# sche_v1.net
KiCad netlist of a schematic drawn in Altium Designer
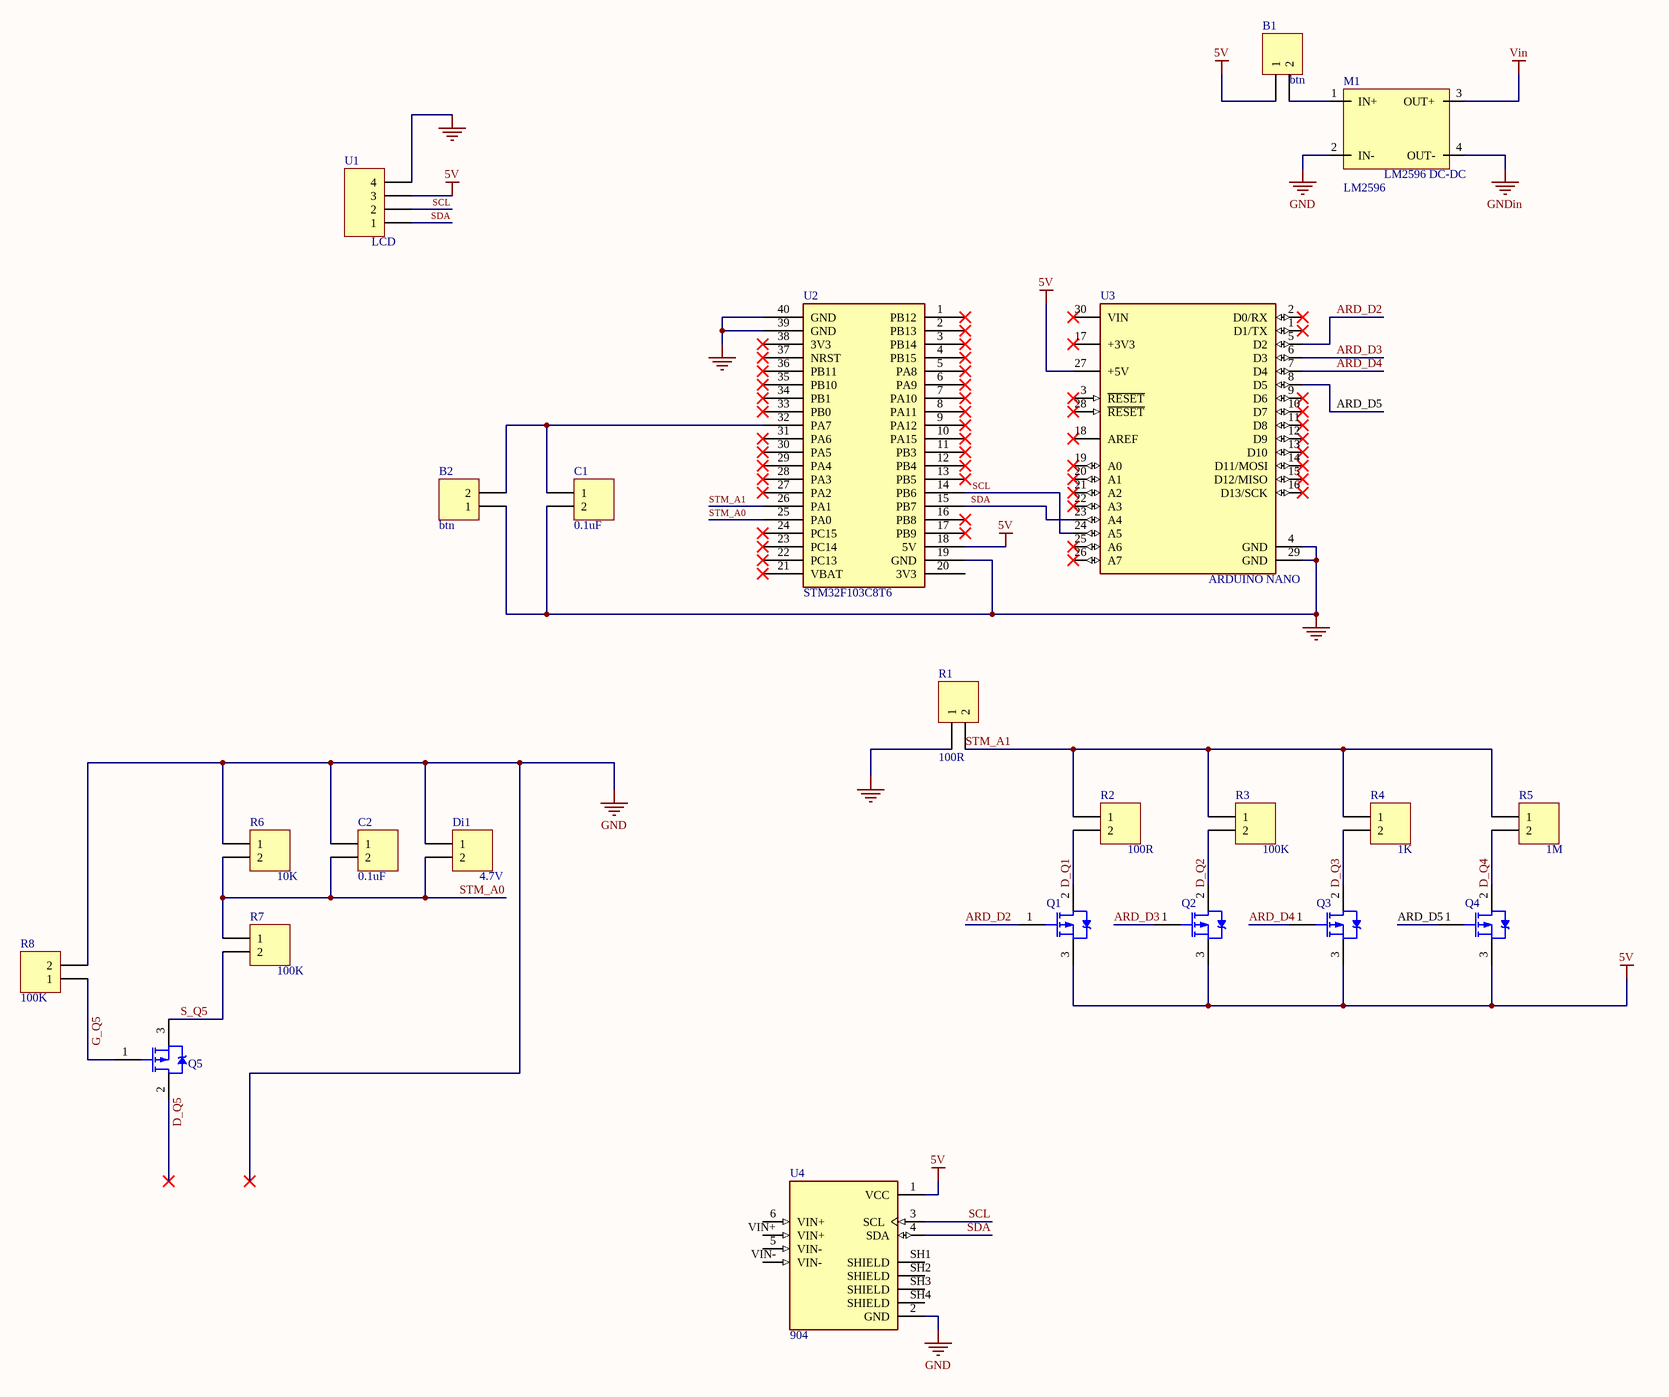
[diagram p0: sche_v1.SchDoc]

(export (version "E")
  (design (tool "Eeschema 10.0.6"))
  (components
    (comp (ref "B1")
      (value "btn")
      (footprint "JP2")
      (description "Header, 2-Pin")
      (fields (field (name "PUBLISHER") "Altium Limited"))
      (libsource (lib "") (part "Header 2_1"))
    )
    (comp (ref "B2")
      (value "btn")
      (footprint "JP2")
      (description "Header, 2-Pin")
      (fields (field (name "PUBLISHER") "Altium Limited"))
      (libsource (lib "") (part "Header 2_2"))
    )
    (comp (ref "C1")
      (value "0.1uF")
      (footprint "JP2")
      (description "Header, 2-Pin")
      (fields (field (name "PUBLISHER") "Altium Limited"))
      (libsource (lib "PIF_Library") (part "Header 2"))
    )
    (comp (ref "C2")
      (value "0.1uF")
      (footprint "JP2")
      (description "Header, 2-Pin")
      (fields (field (name "PUBLISHER") "Altium Limited"))
      (libsource (lib "PIF_Library") (part "Header 2"))
    )
    (comp (ref "Di1")
      (value "4.7V")
      (footprint "JP2")
      (description "Header, 2-Pin")
      (fields (field (name "PUBLISHER") "Altium Limited"))
      (libsource (lib "PIF_Library") (part "Header 2"))
    )
    (comp (ref "M1")
      (value "LM2596")
      (footprint "LM2596")
      (description "Module")
      (libsource (lib "LM2596") (part "LM2596"))
    )
    (comp (ref "Q1")
      (value "IRF9540N")
      (footprint "IRF9540N-TO-220AB")
      (description "MOSFET P-CH, 100V, 23A, 117mOhm, TO220AB")
      (libsource (lib "Altium_MOSFET") (part "IRF9540N"))
    )
    (comp (ref "Q2")
      (value "IRF9540N")
      (footprint "IRF9540N-TO-220AB")
      (description "MOSFET P-CH, 100V, 23A, 117mOhm, TO220AB")
      (libsource (lib "Altium_MOSFET") (part "IRF9540N"))
    )
    (comp (ref "Q3")
      (value "IRF9540N")
      (footprint "IRF9540N-TO-220AB")
      (description "MOSFET P-CH, 100V, 23A, 117mOhm, TO220AB")
      (libsource (lib "Altium_MOSFET") (part "IRF9540N"))
    )
    (comp (ref "Q4")
      (value "IRF9540N")
      (footprint "IRF9540N-TO-220AB")
      (description "MOSFET P-CH, 100V, 23A, 117mOhm, TO220AB")
      (libsource (lib "Altium_MOSFET") (part "IRF9540N"))
    )
    (comp (ref "Q5")
      (value "IRF9540N")
      (footprint "IRF9540N-TO-220AB")
      (description "MOSFET P-CH, 100V, 23A, 117mOhm, TO220AB")
      (libsource (lib "Altium_MOSFET") (part "IRF9540N"))
    )
    (comp (ref "R1")
      (value "100R")
      (footprint "JP2")
      (description "Header, 2-Pin")
      (fields (field (name "PUBLISHER") "Altium Limited"))
      (libsource (lib "") (part "Header 2_1"))
    )
    (comp (ref "R2")
      (value "100R")
      (footprint "JP2")
      (description "Header, 2-Pin")
      (fields (field (name "PUBLISHER") "Altium Limited"))
      (libsource (lib "PIF_Library") (part "Header 2"))
    )
    (comp (ref "R3")
      (value "100K")
      (footprint "JP2")
      (description "Header, 2-Pin")
      (fields (field (name "PUBLISHER") "Altium Limited"))
      (libsource (lib "PIF_Library") (part "Header 2"))
    )
    (comp (ref "R4")
      (value "1K")
      (footprint "JP2")
      (description "Header, 2-Pin")
      (fields (field (name "PUBLISHER") "Altium Limited"))
      (libsource (lib "PIF_Library") (part "Header 2"))
    )
    (comp (ref "R5")
      (value "1M")
      (footprint "JP2")
      (description "Header, 2-Pin")
      (fields (field (name "PUBLISHER") "Altium Limited"))
      (libsource (lib "PIF_Library") (part "Header 2"))
    )
    (comp (ref "R6")
      (value "10K")
      (footprint "JP2")
      (description "Header, 2-Pin")
      (fields (field (name "PUBLISHER") "Altium Limited"))
      (libsource (lib "PIF_Library") (part "Header 2"))
    )
    (comp (ref "R7")
      (value "100K")
      (footprint "JP2")
      (description "Header, 2-Pin")
      (fields (field (name "PUBLISHER") "Altium Limited"))
      (libsource (lib "PIF_Library") (part "Header 2"))
    )
    (comp (ref "R8")
      (value "100K")
      (footprint "JP2")
      (description "Header, 2-Pin")
      (fields (field (name "PUBLISHER") "Altium Limited"))
      (libsource (lib "") (part "Header 2_2"))
    )
    (comp (ref "U1")
      (value "LCD")
      (footprint "JP4")
      (description "Header, 4-Pin")
      (fields (field (name "PUBLISHER") "Altium Limited"))
      (libsource (lib "PIF_Library") (part "Header 4"))
    )
    (comp (ref "U2")
      (value "STM32F103C8T6")
      (footprint "Stm32 BluePill")
      (description "Designed By @Alixahedi")
      (libsource (lib "Stm32 Blue Pill") (part "BluePill"))
    )
    (comp (ref "U3")
      (value "ARDUINO NANO")
      (footprint "FP-A000005-MFG")
      (description "ARDUINO NANO ATMEGA328 EVAL BRD")
      (libsource (lib "Altium Content Vault") (part "d190c066e99afd1c6882cf92e11b2cc"))
    )
    (comp (ref "U4")
      (value "904")
      (footprint "MODULE_904")
      (fields (field (name "MF") "Adafruit Industries"))
      (libsource (lib "904") (part "904"))
    )
  )
  (nets
    (net (code "1") (name "/ARD_D2") (class "Default")
      (node (ref "Q1") (pin "1") (pinfunction "G_1") (pintype "passive"))
      (node (ref "U3") (pin "5") (pinfunction "D2_5") (pintype "bidirectional"))
    )
    (net (code "2") (name "/ARD_D3") (class "Default")
      (node (ref "Q2") (pin "1") (pinfunction "G_1") (pintype "passive"))
      (node (ref "U3") (pin "6") (pinfunction "D3_6") (pintype "bidirectional"))
    )
    (net (code "3") (name "/ARD_D4") (class "Default")
      (node (ref "Q3") (pin "1") (pinfunction "G_1") (pintype "passive"))
      (node (ref "U3") (pin "7") (pinfunction "D4_7") (pintype "bidirectional"))
    )
    (net (code "4") (name "/ARD_D5") (class "Default")
      (node (ref "Q4") (pin "1") (pinfunction "G_1") (pintype "passive"))
      (node (ref "U3") (pin "8") (pinfunction "D5_8") (pintype "bidirectional"))
    )
    (net (code "5") (name "/D_Q1") (class "Default")
      (node (ref "Q1") (pin "2") (pinfunction "D_2") (pintype "passive"))
      (node (ref "R2") (pin "2") (pinfunction "2_2") (pintype "passive"))
    )
    (net (code "6") (name "/D_Q2") (class "Default")
      (node (ref "Q2") (pin "2") (pinfunction "D_2") (pintype "passive"))
      (node (ref "R3") (pin "2") (pinfunction "2_2") (pintype "passive"))
    )
    (net (code "7") (name "/D_Q3") (class "Default")
      (node (ref "Q3") (pin "2") (pinfunction "D_2") (pintype "passive"))
      (node (ref "R4") (pin "2") (pinfunction "2_2") (pintype "passive"))
    )
    (net (code "8") (name "/D_Q4") (class "Default")
      (node (ref "Q4") (pin "2") (pinfunction "D_2") (pintype "passive"))
      (node (ref "R5") (pin "2") (pinfunction "2_2") (pintype "passive"))
    )
    (net (code "9") (name "/D_Q5") (class "Default")
      (node (ref "Q5") (pin "2") (pinfunction "D_2") (pintype "passive+no_connect"))
    )
    (net (code "10") (name "/G_Q5") (class "Default")
      (node (ref "Q5") (pin "1") (pinfunction "G_1") (pintype "passive"))
      (node (ref "R8") (pin "1") (pinfunction "1_1") (pintype "passive"))
    )
    (net (code "11") (name "/SCL") (class "Default")
      (node (ref "U1") (pin "2") (pinfunction "2_2") (pintype "passive"))
      (node (ref "U2") (pin "14") (pinfunction "PB6_14") (pintype "passive"))
      (node (ref "U3") (pin "24") (pinfunction "A5_24") (pintype "bidirectional"))
      (node (ref "U4") (pin "3") (pinfunction "SCL_3") (pintype "input"))
    )
    (net (code "12") (name "/SDA") (class "Default")
      (node (ref "U1") (pin "1") (pinfunction "1_1") (pintype "passive"))
      (node (ref "U2") (pin "15") (pinfunction "PB7_15") (pintype "passive"))
      (node (ref "U3") (pin "23") (pinfunction "A4_23") (pintype "bidirectional"))
      (node (ref "U4") (pin "4") (pinfunction "SDA_4") (pintype "bidirectional"))
    )
    (net (code "13") (name "/STM_A0") (class "Default")
      (node (ref "C2") (pin "2") (pinfunction "2_2") (pintype "passive"))
      (node (ref "Di1") (pin "2") (pinfunction "2_2") (pintype "passive"))
      (node (ref "R6") (pin "2") (pinfunction "2_2") (pintype "passive"))
      (node (ref "R7") (pin "1") (pinfunction "1_1") (pintype "passive"))
      (node (ref "U2") (pin "25") (pinfunction "PA0_25") (pintype "passive"))
    )
    (net (code "14") (name "/STM_A1") (class "Default")
      (node (ref "R1") (pin "2") (pinfunction "2_2") (pintype "passive"))
      (node (ref "R2") (pin "1") (pinfunction "1_1") (pintype "passive"))
      (node (ref "R3") (pin "1") (pinfunction "1_1") (pintype "passive"))
      (node (ref "R4") (pin "1") (pinfunction "1_1") (pintype "passive"))
      (node (ref "R5") (pin "1") (pinfunction "1_1") (pintype "passive"))
      (node (ref "U2") (pin "26") (pinfunction "PA1_26") (pintype "passive"))
    )
    (net (code "15") (name "/S_Q5") (class "Default")
      (node (ref "Q5") (pin "3") (pinfunction "S_3") (pintype "passive"))
      (node (ref "R7") (pin "2") (pinfunction "2_2") (pintype "passive"))
    )
    (net (code "16") (name "5V") (class "Default")
      (node (ref "B1") (pin "1") (pinfunction "1_1") (pintype "passive"))
      (node (ref "Q1") (pin "3") (pinfunction "S_3") (pintype "passive"))
      (node (ref "Q2") (pin "3") (pinfunction "S_3") (pintype "passive"))
      (node (ref "Q3") (pin "3") (pinfunction "S_3") (pintype "passive"))
      (node (ref "Q4") (pin "3") (pinfunction "S_3") (pintype "passive"))
      (node (ref "U1") (pin "3") (pinfunction "3_3") (pintype "passive"))
      (node (ref "U2") (pin "18") (pinfunction "5V_18") (pintype "passive"))
      (node (ref "U3") (pin "27") (pinfunction "+5V_27") (pintype "power_in"))
      (node (ref "U4") (pin "1") (pinfunction "VCC_1") (pintype "power_in"))
    )
    (net (code "17") (name "GND") (class "Default")
      (node (ref "B2") (pin "1") (pinfunction "1_1") (pintype "passive"))
      (node (ref "C1") (pin "2") (pinfunction "2_2") (pintype "passive"))
      (node (ref "C2") (pin "1") (pinfunction "1_1") (pintype "passive"))
      (node (ref "Di1") (pin "1") (pinfunction "1_1") (pintype "passive"))
      (node (ref "M1") (pin "2") (pinfunction "IN-_2") (pintype "power_in"))
      (node (ref "R1") (pin "1") (pinfunction "1_1") (pintype "passive"))
      (node (ref "R6") (pin "1") (pinfunction "1_1") (pintype "passive"))
      (node (ref "R8") (pin "2") (pinfunction "2_2") (pintype "passive"))
      (node (ref "U1") (pin "4") (pinfunction "4_4") (pintype "passive"))
      (node (ref "U2") (pin "19") (pinfunction "GND_19") (pintype "passive"))
      (node (ref "U2") (pin "39") (pinfunction "GND_39") (pintype "passive"))
      (node (ref "U2") (pin "40") (pinfunction "GND_40") (pintype "passive"))
      (node (ref "U3") (pin "29") (pinfunction "GND_29") (pintype "power_in"))
      (node (ref "U3") (pin "4") (pinfunction "GND_4") (pintype "power_in"))
      (node (ref "U4") (pin "2") (pinfunction "GND_2") (pintype "power_in"))
    )
    (net (code "18") (name "GNDin") (class "Default")
      (node (ref "M1") (pin "4") (pinfunction "OUT-_4") (pintype "passive"))
    )
    (net (code "19") (name "Net-(M1-IN+)") (class "Default")
      (node (ref "B1") (pin "2") (pinfunction "2_2") (pintype "passive"))
      (node (ref "M1") (pin "1") (pinfunction "IN+_1") (pintype "power_in"))
    )
    (net (code "20") (name "Net-(U2-PA7)") (class "Default")
      (node (ref "B2") (pin "2") (pinfunction "2_2") (pintype "passive"))
      (node (ref "C1") (pin "1") (pinfunction "1_1") (pintype "passive"))
      (node (ref "U2") (pin "32") (pinfunction "PA7_32") (pintype "passive"))
    )
    (net (code "21") (name "Vin") (class "Default")
      (node (ref "M1") (pin "3") (pinfunction "OUT+_3") (pintype "power_in"))
    )
    (net (code "22") (name "unconnected-(U2-3V3-Pad20)") (class "Default")
      (node (ref "U2") (pin "20") (pinfunction "3V3_20") (pintype "passive"))
    )
    (net (code "23") (name "unconnected-(U2-3V3-Pad38)") (class "Default")
      (node (ref "U2") (pin "38") (pinfunction "3V3_38") (pintype "passive+no_connect"))
    )
    (net (code "24") (name "unconnected-(U2-NRST-Pad37)") (class "Default")
      (node (ref "U2") (pin "37") (pinfunction "NRST_37") (pintype "passive+no_connect"))
    )
    (net (code "25") (name "unconnected-(U2-PA2-Pad27)") (class "Default")
      (node (ref "U2") (pin "27") (pinfunction "PA2_27") (pintype "passive+no_connect"))
    )
    (net (code "26") (name "unconnected-(U2-PA3-Pad28)") (class "Default")
      (node (ref "U2") (pin "28") (pinfunction "PA3_28") (pintype "passive+no_connect"))
    )
    (net (code "27") (name "unconnected-(U2-PA4-Pad29)") (class "Default")
      (node (ref "U2") (pin "29") (pinfunction "PA4_29") (pintype "passive+no_connect"))
    )
    (net (code "28") (name "unconnected-(U2-PA5-Pad30)") (class "Default")
      (node (ref "U2") (pin "30") (pinfunction "PA5_30") (pintype "passive+no_connect"))
    )
    (net (code "29") (name "unconnected-(U2-PA6-Pad31)") (class "Default")
      (node (ref "U2") (pin "31") (pinfunction "PA6_31") (pintype "passive+no_connect"))
    )
    (net (code "30") (name "unconnected-(U2-PA8-Pad5)") (class "Default")
      (node (ref "U2") (pin "5") (pinfunction "PA8_5") (pintype "passive+no_connect"))
    )
    (net (code "31") (name "unconnected-(U2-PA9-Pad6)") (class "Default")
      (node (ref "U2") (pin "6") (pinfunction "PA9_6") (pintype "passive+no_connect"))
    )
    (net (code "32") (name "unconnected-(U2-PA10-Pad7)") (class "Default")
      (node (ref "U2") (pin "7") (pinfunction "PA10_7") (pintype "passive+no_connect"))
    )
    (net (code "33") (name "unconnected-(U2-PA11-Pad8)") (class "Default")
      (node (ref "U2") (pin "8") (pinfunction "PA11_8") (pintype "passive+no_connect"))
    )
    (net (code "34") (name "unconnected-(U2-PA12-Pad9)") (class "Default")
      (node (ref "U2") (pin "9") (pinfunction "PA12_9") (pintype "passive+no_connect"))
    )
    (net (code "35") (name "unconnected-(U2-PA15-Pad10)") (class "Default")
      (node (ref "U2") (pin "10") (pinfunction "PA15_10") (pintype "passive+no_connect"))
    )
    (net (code "36") (name "unconnected-(U2-PB0-Pad33)") (class "Default")
      (node (ref "U2") (pin "33") (pinfunction "PB0_33") (pintype "passive+no_connect"))
    )
    (net (code "37") (name "unconnected-(U2-PB1-Pad34)") (class "Default")
      (node (ref "U2") (pin "34") (pinfunction "PB1_34") (pintype "passive+no_connect"))
    )
    (net (code "38") (name "unconnected-(U2-PB3-Pad11)") (class "Default")
      (node (ref "U2") (pin "11") (pinfunction "PB3_11") (pintype "passive+no_connect"))
    )
    (net (code "39") (name "unconnected-(U2-PB4-Pad12)") (class "Default")
      (node (ref "U2") (pin "12") (pinfunction "PB4_12") (pintype "passive+no_connect"))
    )
    (net (code "40") (name "unconnected-(U2-PB5-Pad13)") (class "Default")
      (node (ref "U2") (pin "13") (pinfunction "PB5_13") (pintype "passive+no_connect"))
    )
    (net (code "41") (name "unconnected-(U2-PB8-Pad16)") (class "Default")
      (node (ref "U2") (pin "16") (pinfunction "PB8_16") (pintype "passive+no_connect"))
    )
    (net (code "42") (name "unconnected-(U2-PB9-Pad17)") (class "Default")
      (node (ref "U2") (pin "17") (pinfunction "PB9_17") (pintype "passive+no_connect"))
    )
    (net (code "43") (name "unconnected-(U2-PB10-Pad35)") (class "Default")
      (node (ref "U2") (pin "35") (pinfunction "PB10_35") (pintype "passive+no_connect"))
    )
    (net (code "44") (name "unconnected-(U2-PB11-Pad36)") (class "Default")
      (node (ref "U2") (pin "36") (pinfunction "PB11_36") (pintype "passive+no_connect"))
    )
    (net (code "45") (name "unconnected-(U2-PB12-Pad1)") (class "Default")
      (node (ref "U2") (pin "1") (pinfunction "PB12_1") (pintype "passive+no_connect"))
    )
    (net (code "46") (name "unconnected-(U2-PB13-Pad2)") (class "Default")
      (node (ref "U2") (pin "2") (pinfunction "PB13_2") (pintype "passive+no_connect"))
    )
    (net (code "47") (name "unconnected-(U2-PB14-Pad3)") (class "Default")
      (node (ref "U2") (pin "3") (pinfunction "PB14_3") (pintype "passive+no_connect"))
    )
    (net (code "48") (name "unconnected-(U2-PB15-Pad4)") (class "Default")
      (node (ref "U2") (pin "4") (pinfunction "PB15_4") (pintype "passive+no_connect"))
    )
    (net (code "49") (name "unconnected-(U2-PC13-Pad22)") (class "Default")
      (node (ref "U2") (pin "22") (pinfunction "PC13_22") (pintype "passive+no_connect"))
    )
    (net (code "50") (name "unconnected-(U2-PC14-Pad23)") (class "Default")
      (node (ref "U2") (pin "23") (pinfunction "PC14_23") (pintype "passive+no_connect"))
    )
    (net (code "51") (name "unconnected-(U2-PC15-Pad24)") (class "Default")
      (node (ref "U2") (pin "24") (pinfunction "PC15_24") (pintype "passive+no_connect"))
    )
    (net (code "52") (name "unconnected-(U2-VBAT-Pad21)") (class "Default")
      (node (ref "U2") (pin "21") (pinfunction "VBAT_21") (pintype "passive+no_connect"))
    )
    (net (code "53") (name "unconnected-(U3-+3V3-Pad17)") (class "Default")
      (node (ref "U3") (pin "17") (pinfunction "+3V3_17") (pintype "power_in+no_connect"))
    )
    (net (code "54") (name "unconnected-(U3-A0-Pad19)") (class "Default")
      (node (ref "U3") (pin "19") (pinfunction "A0_19") (pintype "bidirectional+no_connect"))
    )
    (net (code "55") (name "unconnected-(U3-A1-Pad20)") (class "Default")
      (node (ref "U3") (pin "20") (pinfunction "A1_20") (pintype "bidirectional+no_connect"))
    )
    (net (code "56") (name "unconnected-(U3-A2-Pad21)") (class "Default")
      (node (ref "U3") (pin "21") (pinfunction "A2_21") (pintype "bidirectional+no_connect"))
    )
    (net (code "57") (name "unconnected-(U3-A3-Pad22)") (class "Default")
      (node (ref "U3") (pin "22") (pinfunction "A3_22") (pintype "bidirectional+no_connect"))
    )
    (net (code "58") (name "unconnected-(U3-A6-Pad25)") (class "Default")
      (node (ref "U3") (pin "25") (pinfunction "A6_25") (pintype "bidirectional+no_connect"))
    )
    (net (code "59") (name "unconnected-(U3-A7-Pad26)") (class "Default")
      (node (ref "U3") (pin "26") (pinfunction "A7_26") (pintype "bidirectional+no_connect"))
    )
    (net (code "60") (name "unconnected-(U3-AREF-Pad18)") (class "Default")
      (node (ref "U3") (pin "18") (pinfunction "AREF_18") (pintype "passive+no_connect"))
    )
    (net (code "61") (name "unconnected-(U3-D0{slash}RX-Pad2)") (class "Default")
      (node (ref "U3") (pin "2") (pinfunction "D0/RX_2") (pintype "bidirectional+no_connect"))
    )
    (net (code "62") (name "unconnected-(U3-D1{slash}TX-Pad1)") (class "Default")
      (node (ref "U3") (pin "1") (pinfunction "D1/TX_1") (pintype "bidirectional+no_connect"))
    )
    (net (code "63") (name "unconnected-(U3-D6-Pad9)") (class "Default")
      (node (ref "U3") (pin "9") (pinfunction "D6_9") (pintype "bidirectional+no_connect"))
    )
    (net (code "64") (name "unconnected-(U3-D7-Pad10)") (class "Default")
      (node (ref "U3") (pin "10") (pinfunction "D7_10") (pintype "bidirectional+no_connect"))
    )
    (net (code "65") (name "unconnected-(U3-D8-Pad11)") (class "Default")
      (node (ref "U3") (pin "11") (pinfunction "D8_11") (pintype "bidirectional+no_connect"))
    )
    (net (code "66") (name "unconnected-(U3-D9-Pad12)") (class "Default")
      (node (ref "U3") (pin "12") (pinfunction "D9_12") (pintype "bidirectional+no_connect"))
    )
    (net (code "67") (name "unconnected-(U3-D10-Pad13)") (class "Default")
      (node (ref "U3") (pin "13") (pinfunction "D10_13") (pintype "bidirectional+no_connect"))
    )
    (net (code "68") (name "unconnected-(U3-D11{slash}MOSI-Pad14)") (class "Default")
      (node (ref "U3") (pin "14") (pinfunction "D11/MOSI_14") (pintype "bidirectional+no_connect"))
    )
    (net (code "69") (name "unconnected-(U3-D12{slash}MISO-Pad15)") (class "Default")
      (node (ref "U3") (pin "15") (pinfunction "D12/MISO_15") (pintype "bidirectional+no_connect"))
    )
    (net (code "70") (name "unconnected-(U3-D13{slash}SCK-Pad16)") (class "Default")
      (node (ref "U3") (pin "16") (pinfunction "D13/SCK_16") (pintype "bidirectional+no_connect"))
    )
    (net (code "71") (name "unconnected-(U3-VIN-Pad30)") (class "Default")
      (node (ref "U3") (pin "30") (pinfunction "VIN_30") (pintype "power_in+no_connect"))
    )
    (net (code "72") (name "unconnected-(U3-~{RESET}-Pad3)") (class "Default")
      (node (ref "U3") (pin "3") (pinfunction "~{RESET}_3") (pintype "input+no_connect"))
    )
    (net (code "73") (name "unconnected-(U3-~{RESET}-Pad28)") (class "Default")
      (node (ref "U3") (pin "28") (pinfunction "~{RESET}_28") (pintype "input+no_connect"))
    )
    (net (code "74") (name "unconnected-(U4-PadVIN+)") (class "Default")
      (node (ref "U4") (pin "VIN+") (pinfunction "VIN+_VIN+") (pintype "input"))
    )
    (net (code "75") (name "unconnected-(U4-PadVIN-)") (class "Default")
      (node (ref "U4") (pin "VIN-") (pinfunction "VIN-_VIN-") (pintype "input"))
    )
    (net (code "76") (name "unconnected-(U4-SHIELD-PadSH1)") (class "Default")
      (node (ref "U4") (pin "SH1") (pinfunction "SHIELD_SH1") (pintype "passive"))
    )
    (net (code "77") (name "unconnected-(U4-SHIELD-PadSH2)") (class "Default")
      (node (ref "U4") (pin "SH2") (pinfunction "SHIELD_SH2") (pintype "passive"))
    )
    (net (code "78") (name "unconnected-(U4-SHIELD-PadSH3)") (class "Default")
      (node (ref "U4") (pin "SH3") (pinfunction "SHIELD_SH3") (pintype "passive"))
    )
    (net (code "79") (name "unconnected-(U4-SHIELD-PadSH4)") (class "Default")
      (node (ref "U4") (pin "SH4") (pinfunction "SHIELD_SH4") (pintype "passive"))
    )
    (net (code "80") (name "unconnected-(U4-VIN+-Pad6)") (class "Default")
      (node (ref "U4") (pin "6") (pinfunction "VIN+_6") (pintype "input"))
    )
    (net (code "81") (name "unconnected-(U4-VIN--Pad5)") (class "Default")
      (node (ref "U4") (pin "5") (pinfunction "VIN-_5") (pintype "input"))
    )
  )
)
